# IR2104_7.net
KiCad netlist of a schematic drawn in Altium Designer
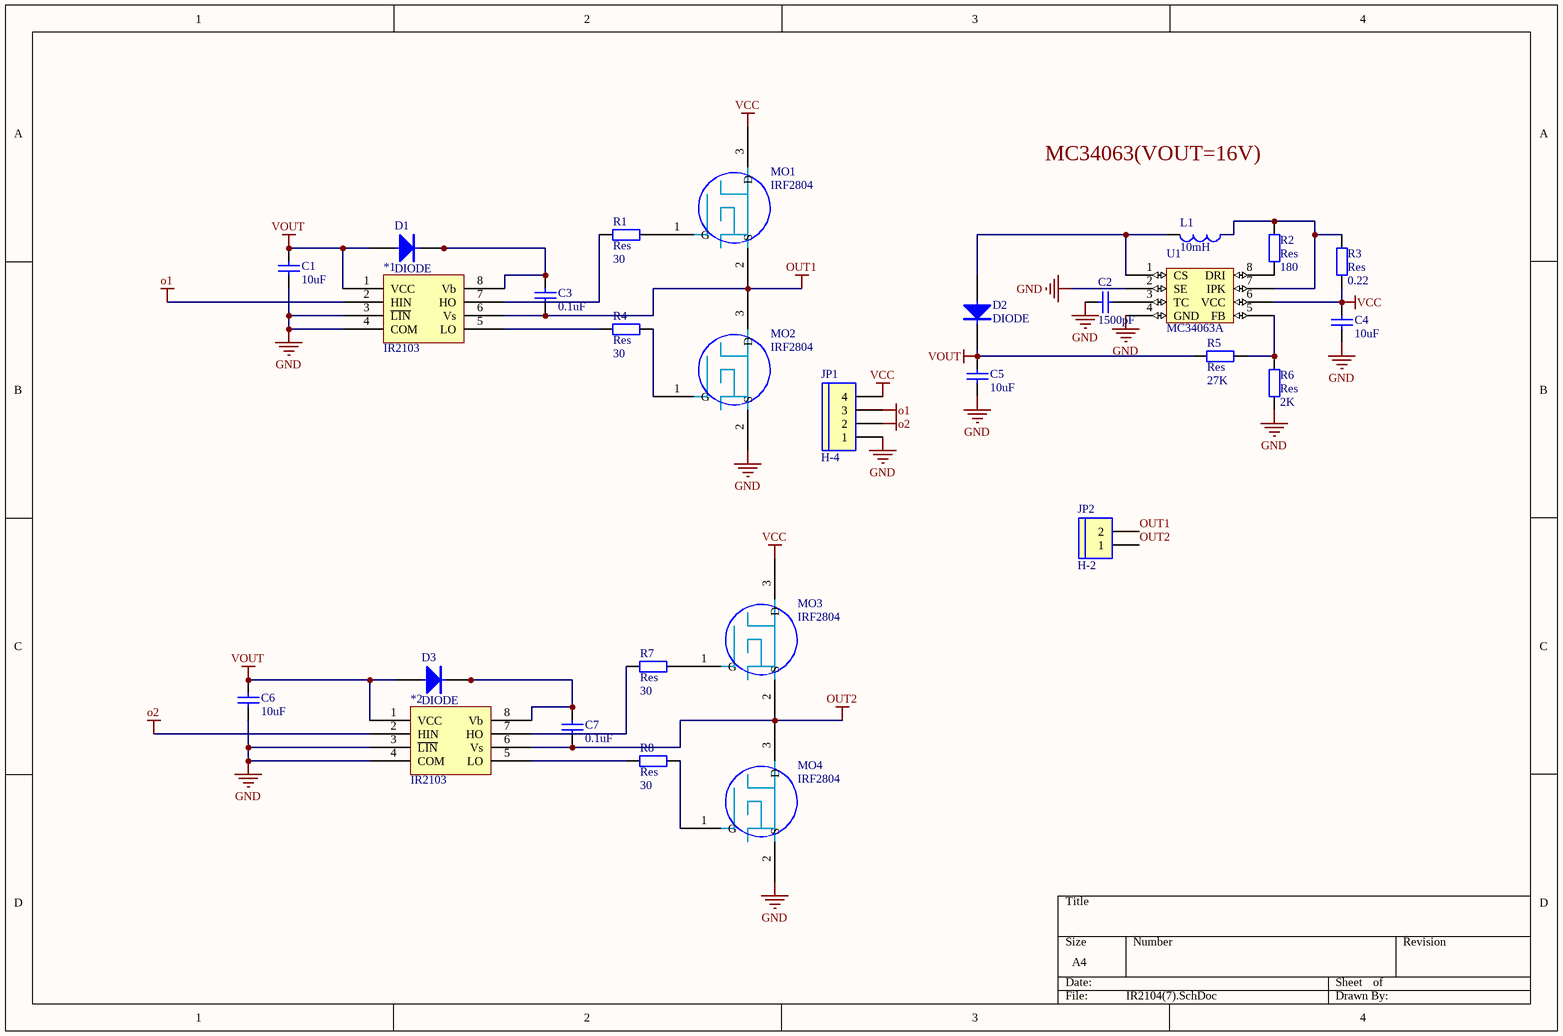
[diagram p0: IR2104(7).SchDoc]

(export (version "E")
  (design (tool "Eeschema 10.0.6"))
  (components
    (comp (ref "*1") (value "IR2103") (footprint "IR2104S") (libsource (lib "My SchLib") (part "IR2103")))
    (comp (ref "*2") (value "IR2103") (footprint "IR2104S") (libsource (lib "My SchLib") (part "IR2103")))
    (comp (ref "C1")
      (value "10uF")
      (footprint "CC1005-0402")
      (description "Capacitor")
      (fields
        (field (name "MANUFACTURER") "Generic Components")
        (field (name "Comment") "CAP_1")
        (field (name "PUBLISHER") "Altium Hobart Technology Centre")
      )
      (libsource (lib "My SchLib") (part "CAP_1"))
    )
    (comp (ref "C2")
      (value "1500pF")
      (footprint "CC1005-0402")
      (description "Capacitor")
      (fields
        (field (name "MANUFACTURER") "Generic Components")
        (field (name "Comment") "CAP_1")
        (field (name "PUBLISHER") "Altium Hobart Technology Centre")
      )
      (libsource (lib "My SchLib") (part "CAP_1"))
    )
    (comp (ref "C3")
      (value "0.1uF")
      (footprint "CC1005-0402")
      (description "Capacitor")
      (fields
        (field (name "MANUFACTURER") "Generic Components")
        (field (name "Comment") "CAP_1")
        (field (name "PUBLISHER") "Altium Hobart Technology Centre")
      )
      (libsource (lib "My SchLib") (part "CAP_1"))
    )
    (comp (ref "C4")
      (value "10uF")
      (footprint "CC1005-0402")
      (description "Capacitor")
      (fields
        (field (name "MANUFACTURER") "Generic Components")
        (field (name "Comment") "CAP_1")
        (field (name "PUBLISHER") "Altium Hobart Technology Centre")
      )
      (libsource (lib "My SchLib") (part "CAP_1"))
    )
    (comp (ref "C5")
      (value "10uF")
      (footprint "CC1005-0402")
      (description "Capacitor")
      (fields
        (field (name "MANUFACTURER") "Generic Components")
        (field (name "Comment") "CAP_1")
        (field (name "PUBLISHER") "Altium Hobart Technology Centre")
      )
      (libsource (lib "My SchLib") (part "CAP_1"))
    )
    (comp (ref "C6")
      (value "10uF")
      (footprint "CC1005-0402")
      (description "Capacitor")
      (fields
        (field (name "MANUFACTURER") "Generic Components")
        (field (name "Comment") "CAP_1")
        (field (name "PUBLISHER") "Altium Hobart Technology Centre")
      )
      (libsource (lib "My SchLib") (part "CAP_1"))
    )
    (comp (ref "C7")
      (value "0.1uF")
      (footprint "CC1005-0402")
      (description "Capacitor")
      (fields
        (field (name "MANUFACTURER") "Generic Components")
        (field (name "Comment") "CAP_1")
        (field (name "PUBLISHER") "Altium Hobart Technology Centre")
      )
      (libsource (lib "My SchLib") (part "CAP_1"))
    )
    (comp (ref "D1") (value "DIODE") (footprint "diode stan") (libsource (lib "我的库") (part "DIODE")))
    (comp (ref "D2") (value "DIODE") (footprint "diode stan") (libsource (lib "我的库") (part "DIODE")))
    (comp (ref "D3") (value "DIODE") (footprint "diode stan") (libsource (lib "我的库") (part "DIODE")))
    (comp (ref "JP1")
      (value "H-4")
      (footprint "H-4/4 -T")
      (description "Header, 4-Pin")
      (fields (field (name "MANUFACTURER") "Generic Components"))
      (libsource (lib "My SchLib") (part "H-4"))
    )
    (comp (ref "JP2")
      (value "H-2")
      (footprint "H-2/2-T")
      (description "Header, 2-Pin")
      (fields (field (name "MANUFACTURER") "Generic Components"))
      (libsource (lib "My SchLib") (part "H-2"))
    )
    (comp (ref "L1") (value "10mH") (footprint "贴片电感") (libsource (lib "我的库") (part "INDUCTOR")))
    (comp (ref "MO1")
      (value "IRF2804")
      (footprint "TS-005")
      (libsource (lib "my integrated library") (part "IRF2804"))
    )
    (comp (ref "MO2")
      (value "IRF2804")
      (footprint "TS-005")
      (libsource (lib "my integrated library") (part "IRF2804"))
    )
    (comp (ref "MO3")
      (value "IRF2804")
      (footprint "TS-005")
      (libsource (lib "my integrated library") (part "IRF2804"))
    )
    (comp (ref "MO4")
      (value "IRF2804")
      (footprint "TS-005")
      (libsource (lib "my integrated library") (part "IRF2804"))
    )
    (comp (ref "R1")
      (value "Res")
      (footprint "R2012-0805")
      (description "Resistor")
      (fields
        (field (name "MANUFACTURER") "Generic Components")
        (field (name "ALTIUM_VALUE") "30")
        (field (name "PUBLISHER") "Altium Hobart Technology Centre")
      )
      (libsource (lib "My SchLib") (part "Res"))
    )
    (comp (ref "R2")
      (value "Res")
      (footprint "R2012-0805")
      (description "Resistor")
      (fields
        (field (name "MANUFACTURER") "Generic Components")
        (field (name "ALTIUM_VALUE") "180")
        (field (name "PUBLISHER") "Altium Hobart Technology Centre")
      )
      (libsource (lib "") (part "Res_2"))
    )
    (comp (ref "R3")
      (value "Res")
      (footprint "R2012-0805")
      (description "Resistor")
      (fields
        (field (name "MANUFACTURER") "Generic Components")
        (field (name "ALTIUM_VALUE") "0.22")
        (field (name "PUBLISHER") "Altium Hobart Technology Centre")
      )
      (libsource (lib "") (part "Res_1"))
    )
    (comp (ref "R4")
      (value "Res")
      (footprint "R2012-0805")
      (description "Resistor")
      (fields
        (field (name "MANUFACTURER") "Generic Components")
        (field (name "ALTIUM_VALUE") "30")
        (field (name "PUBLISHER") "Altium Hobart Technology Centre")
      )
      (libsource (lib "My SchLib") (part "Res"))
    )
    (comp (ref "R5")
      (value "Res")
      (footprint "R2012-0805")
      (description "Resistor")
      (fields
        (field (name "MANUFACTURER") "Generic Components")
        (field (name "ALTIUM_VALUE") "27K")
        (field (name "PUBLISHER") "Altium Hobart Technology Centre")
      )
      (libsource (lib "My SchLib") (part "Res"))
    )
    (comp (ref "R6")
      (value "Res")
      (footprint "R2012-0805")
      (description "Resistor")
      (fields
        (field (name "MANUFACTURER") "Generic Components")
        (field (name "ALTIUM_VALUE") "2K")
        (field (name "PUBLISHER") "Altium Hobart Technology Centre")
      )
      (libsource (lib "") (part "Res_2"))
    )
    (comp (ref "R7")
      (value "Res")
      (footprint "R2012-0805")
      (description "Resistor")
      (fields
        (field (name "MANUFACTURER") "Generic Components")
        (field (name "ALTIUM_VALUE") "30")
        (field (name "PUBLISHER") "Altium Hobart Technology Centre")
      )
      (libsource (lib "My SchLib") (part "Res"))
    )
    (comp (ref "R8")
      (value "Res")
      (footprint "R2012-0805")
      (description "Resistor")
      (fields
        (field (name "MANUFACTURER") "Generic Components")
        (field (name "ALTIUM_VALUE") "30")
        (field (name "PUBLISHER") "Altium Hobart Technology Centre")
      )
      (libsource (lib "My SchLib") (part "Res"))
    )
    (comp (ref "U1") (value "MC34063A") (footprint "SOP-8") (libsource (lib "My SchLib") (part "MC34063A")))
  )
  (nets
    (net (code "2") (name "GND") (class "Default")
      (node (ref "*1") (pin "3") (pinfunction "~{LIN}_3") (pintype "passive"))
      (node (ref "*1") (pin "4") (pinfunction "COM_4") (pintype "passive"))
      (node (ref "*2") (pin "3") (pinfunction "~{LIN}_3") (pintype "passive"))
      (node (ref "*2") (pin "4") (pinfunction "COM_4") (pintype "passive"))
      (node (ref "C1") (pin "1") (pinfunction "1_1") (pintype "passive"))
      (node (ref "C2") (pin "1") (pinfunction "1_1") (pintype "passive"))
      (node (ref "C4") (pin "1") (pinfunction "1_1") (pintype "passive"))
      (node (ref "C5") (pin "1") (pinfunction "1_1") (pintype "passive"))
      (node (ref "C6") (pin "1") (pinfunction "1_1") (pintype "passive"))
      (node (ref "JP1") (pin "1") (pinfunction "1_1") (pintype "passive"))
      (node (ref "MO2") (pin "2") (pinfunction "S_2") (pintype "passive"))
      (node (ref "MO4") (pin "2") (pinfunction "S_2") (pintype "passive"))
      (node (ref "R6") (pin "1") (pinfunction "1_1") (pintype "passive"))
      (node (ref "U1") (pin "2") (pinfunction "SE_2") (pintype "bidirectional"))
      (node (ref "U1") (pin "4") (pinfunction "GND_4") (pintype "bidirectional"))
    )
    (net (code "3") (name "Net-(*1-HO)") (class "Default")
      (node (ref "*1") (pin "7") (pinfunction "HO_7") (pintype "passive"))
      (node (ref "R1") (pin "1") (pinfunction "1_1") (pintype "passive"))
    )
    (net (code "4") (name "Net-(*1-LO)") (class "Default")
      (node (ref "*1") (pin "5") (pinfunction "LO_5") (pintype "passive"))
      (node (ref "R4") (pin "1") (pinfunction "1_1") (pintype "passive"))
    )
    (net (code "5") (name "Net-(*1-Vb)") (class "Default")
      (node (ref "*1") (pin "8") (pinfunction "Vb_8") (pintype "passive"))
      (node (ref "C3") (pin "2") (pinfunction "2_2") (pintype "passive"))
      (node (ref "D1") (pin "2") (pinfunction "K_2") (pintype "passive"))
    )
    (net (code "6") (name "Net-(*2-HO)") (class "Default")
      (node (ref "*2") (pin "7") (pinfunction "HO_7") (pintype "passive"))
      (node (ref "R7") (pin "1") (pinfunction "1_1") (pintype "passive"))
    )
    (net (code "7") (name "Net-(*2-LO)") (class "Default")
      (node (ref "*2") (pin "5") (pinfunction "LO_5") (pintype "passive"))
      (node (ref "R8") (pin "1") (pinfunction "1_1") (pintype "passive"))
    )
    (net (code "8") (name "Net-(*2-Vb)") (class "Default")
      (node (ref "*2") (pin "8") (pinfunction "Vb_8") (pintype "passive"))
      (node (ref "C7") (pin "2") (pinfunction "2_2") (pintype "passive"))
      (node (ref "D3") (pin "2") (pinfunction "K_2") (pintype "passive"))
    )
    (net (code "9") (name "Net-(D2-A)") (class "Default")
      (node (ref "D2") (pin "1") (pinfunction "A_1") (pintype "passive"))
      (node (ref "L1") (pin "1") (pinfunction "1_1") (pintype "passive"))
      (node (ref "U1") (pin "1") (pinfunction "CS_1") (pintype "bidirectional"))
    )
    (net (code "10") (name "Net-(MO1-G)") (class "Default")
      (node (ref "MO1") (pin "1") (pinfunction "G_1") (pintype "passive"))
      (node (ref "R1") (pin "2") (pinfunction "2_2") (pintype "passive"))
    )
    (net (code "11") (name "Net-(MO2-G)") (class "Default")
      (node (ref "MO2") (pin "1") (pinfunction "G_1") (pintype "passive"))
      (node (ref "R4") (pin "2") (pinfunction "2_2") (pintype "passive"))
    )
    (net (code "12") (name "Net-(MO3-G)") (class "Default")
      (node (ref "MO3") (pin "1") (pinfunction "G_1") (pintype "passive"))
      (node (ref "R7") (pin "2") (pinfunction "2_2") (pintype "passive"))
    )
    (net (code "13") (name "Net-(MO4-G)") (class "Default")
      (node (ref "MO4") (pin "1") (pinfunction "G_1") (pintype "passive"))
      (node (ref "R8") (pin "2") (pinfunction "2_2") (pintype "passive"))
    )
    (net (code "14") (name "Net-(U1-DRI)") (class "Default")
      (node (ref "R2") (pin "1") (pinfunction "1_1") (pintype "passive"))
      (node (ref "U1") (pin "8") (pinfunction "DRI_8") (pintype "bidirectional"))
    )
    (net (code "15") (name "Net-(U1-FB)") (class "Default")
      (node (ref "R5") (pin "2") (pinfunction "2_2") (pintype "passive"))
      (node (ref "R6") (pin "2") (pinfunction "2_2") (pintype "passive"))
      (node (ref "U1") (pin "5") (pinfunction "FB_5") (pintype "bidirectional"))
    )
    (net (code "16") (name "Net-(U1-IPK)") (class "Default")
      (node (ref "L1") (pin "2") (pinfunction "2_2") (pintype "passive"))
      (node (ref "R2") (pin "2") (pinfunction "2_2") (pintype "passive"))
      (node (ref "R3") (pin "1") (pinfunction "1_1") (pintype "passive"))
      (node (ref "U1") (pin "7") (pinfunction "IPK_7") (pintype "bidirectional"))
    )
    (net (code "17") (name "Net-(U1-TC)") (class "Default")
      (node (ref "C2") (pin "2") (pinfunction "2_2") (pintype "passive"))
      (node (ref "U1") (pin "3") (pinfunction "TC_3") (pintype "bidirectional"))
    )
    (net (code "18") (name "OUT1") (class "Default")
      (node (ref "*1") (pin "6") (pinfunction "Vs_6") (pintype "passive"))
      (node (ref "C3") (pin "1") (pinfunction "1_1") (pintype "passive"))
      (node (ref "JP2") (pin "2") (pinfunction "2_2") (pintype "passive"))
      (node (ref "MO1") (pin "2") (pinfunction "S_2") (pintype "passive"))
      (node (ref "MO2") (pin "3") (pinfunction "D_3") (pintype "passive"))
    )
    (net (code "19") (name "OUT2") (class "Default")
      (node (ref "*2") (pin "6") (pinfunction "Vs_6") (pintype "passive"))
      (node (ref "C7") (pin "1") (pinfunction "1_1") (pintype "passive"))
      (node (ref "JP2") (pin "1") (pinfunction "1_1") (pintype "passive"))
      (node (ref "MO3") (pin "2") (pinfunction "S_2") (pintype "passive"))
      (node (ref "MO4") (pin "3") (pinfunction "D_3") (pintype "passive"))
    )
    (net (code "20") (name "VCC") (class "Default")
      (node (ref "C4") (pin "2") (pinfunction "2_2") (pintype "passive"))
      (node (ref "JP1") (pin "4") (pinfunction "4_4") (pintype "passive"))
      (node (ref "MO1") (pin "3") (pinfunction "D_3") (pintype "passive"))
      (node (ref "MO3") (pin "3") (pinfunction "D_3") (pintype "passive"))
      (node (ref "R3") (pin "2") (pinfunction "2_2") (pintype "passive"))
      (node (ref "U1") (pin "6") (pinfunction "VCC_6") (pintype "bidirectional"))
    )
    (net (code "21") (name "VOUT") (class "Default")
      (node (ref "*1") (pin "1") (pinfunction "VCC_1") (pintype "passive"))
      (node (ref "*2") (pin "1") (pinfunction "VCC_1") (pintype "passive"))
      (node (ref "C1") (pin "2") (pinfunction "2_2") (pintype "passive"))
      (node (ref "C5") (pin "2") (pinfunction "2_2") (pintype "passive"))
      (node (ref "C6") (pin "2") (pinfunction "2_2") (pintype "passive"))
      (node (ref "D1") (pin "1") (pinfunction "A_1") (pintype "passive"))
      (node (ref "D2") (pin "2") (pinfunction "K_2") (pintype "passive"))
      (node (ref "D3") (pin "1") (pinfunction "A_1") (pintype "passive"))
      (node (ref "R5") (pin "1") (pinfunction "1_1") (pintype "passive"))
    )
    (net (code "22") (name "o1") (class "Default")
      (node (ref "*1") (pin "2") (pinfunction "HIN_2") (pintype "passive"))
      (node (ref "JP1") (pin "3") (pinfunction "3_3") (pintype "passive"))
    )
    (net (code "23") (name "o2") (class "Default")
      (node (ref "*2") (pin "2") (pinfunction "HIN_2") (pintype "passive"))
      (node (ref "JP1") (pin "2") (pinfunction "2_2") (pintype "passive"))
    )
  )
)
